# mother_card_rs_247pm.net
KiCad netlist of a schematic drawn in EAGLE
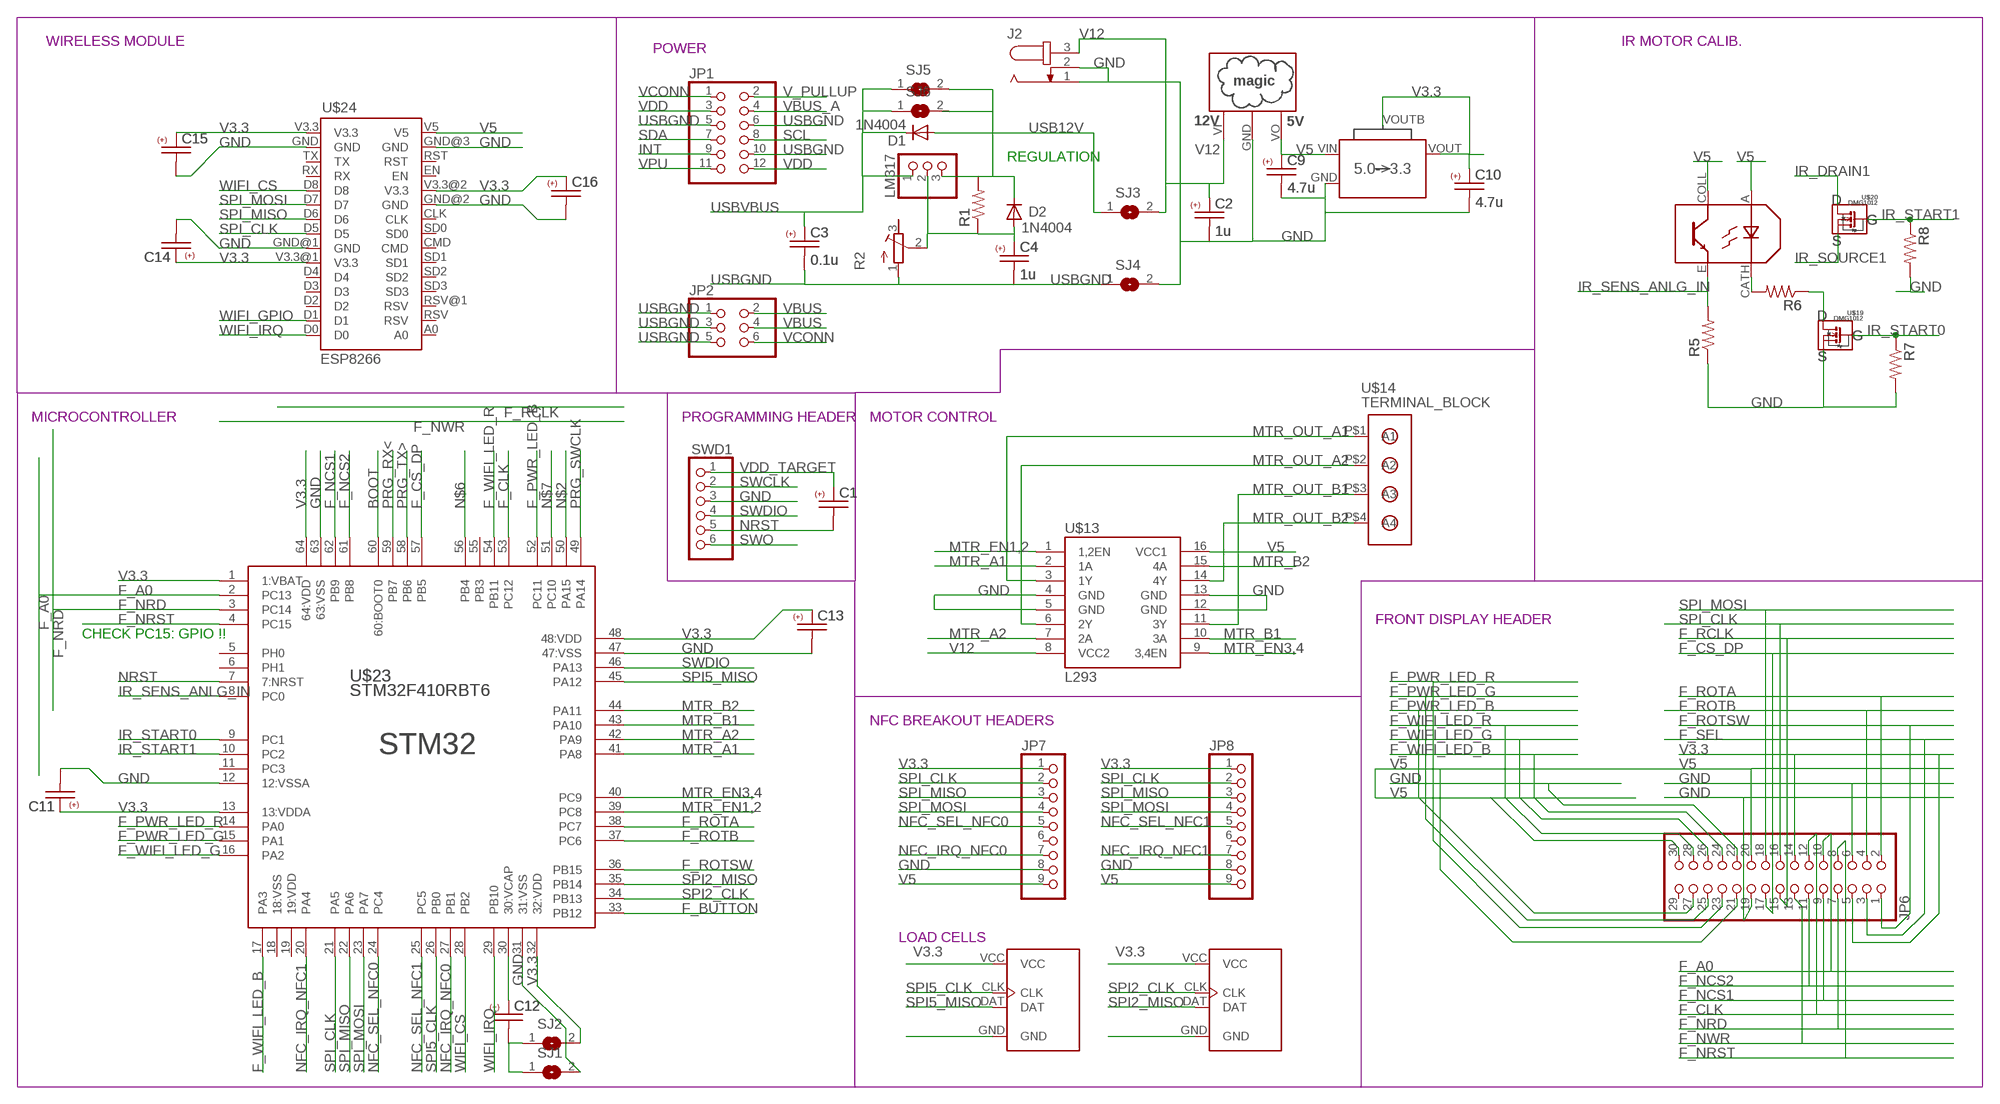
[diagram p0: schematic, sheet 1]

(export (version "E")
  (design (tool "Eeschema 10.0.6"))
  (components
    (comp (ref "C1")
      (value "C-USC0805")
      (footprint "eagle-import:C0805")
      (libsource (lib "eagle-import") (part "C-USC0805"))
    )
    (comp (ref "C2")
      (value "1u")
      (footprint "eagle-import:C0805")
      (libsource (lib "eagle-import") (part "C-USC0805"))
    )
    (comp (ref "C3")
      (value "0.1u")
      (footprint "eagle-import:C0805")
      (libsource (lib "eagle-import") (part "C-USC0805"))
    )
    (comp (ref "C4")
      (value "1u")
      (footprint "eagle-import:C0805")
      (libsource (lib "eagle-import") (part "C-USC0805"))
    )
    (comp (ref "C9")
      (value "4.7u")
      (footprint "eagle-import:C0805")
      (libsource (lib "eagle-import") (part "C-USC0805"))
    )
    (comp (ref "C10")
      (value "4.7u")
      (footprint "eagle-import:C0805")
      (libsource (lib "eagle-import") (part "C-USC0805"))
    )
    (comp (ref "C11")
      (value "C-USC0805")
      (footprint "eagle-import:C0805")
      (libsource (lib "eagle-import") (part "C-USC0805"))
    )
    (comp (ref "C12")
      (value "C-USC0805")
      (footprint "eagle-import:C0805")
      (libsource (lib "eagle-import") (part "C-USC0805"))
    )
    (comp (ref "C13")
      (value "C-USC0805")
      (footprint "eagle-import:C0805")
      (libsource (lib "eagle-import") (part "C-USC0805"))
    )
    (comp (ref "C14")
      (value "C-USC0805")
      (footprint "eagle-import:C0805")
      (libsource (lib "eagle-import") (part "C-USC0805"))
    )
    (comp (ref "C15")
      (value "C-USC0805")
      (footprint "eagle-import:C0805")
      (libsource (lib "eagle-import") (part "C-USC0805"))
    )
    (comp (ref "C16")
      (value "C-USC0805")
      (footprint "eagle-import:C0805")
      (libsource (lib "eagle-import") (part "C-USC0805"))
    )
    (comp (ref "D1")
      (value "1N4004")
      (footprint "eagle-import:DO41-10")
      (libsource (lib "eagle-import") (part "1N4004"))
    )
    (comp (ref "D2")
      (value "1N4004")
      (footprint "eagle-import:DO41-10")
      (libsource (lib "eagle-import") (part "1N4004"))
    )
    (comp (ref "J2")
      (value "JACK-PLUG0")
      (footprint "eagle-import:SPC4077")
      (libsource (lib "eagle-import") (part "JACK-PLUG0"))
    )
    (comp (ref "JP1")
      (value "PINHD-2X6")
      (footprint "eagle-import:2X06")
      (libsource (lib "eagle-import") (part "PINHD-2X6"))
    )
    (comp (ref "JP2")
      (value "PINHD-2X3")
      (footprint "eagle-import:2X03")
      (libsource (lib "eagle-import") (part "PINHD-2X3"))
    )
    (comp (ref "JP6")
      (value "PINHD-2X15/SOCK")
      (footprint "eagle-import:2X15_SOCK")
      (libsource (lib "eagle-import") (part "PINHD-2X15/SOCK"))
    )
    (comp (ref "JP7")
      (value "PINHD-1X9/90")
      (footprint "eagle-import:1X09_90")
      (libsource (lib "eagle-import") (part "PINHD-1X9/90"))
    )
    (comp (ref "JP8")
      (value "PINHD-1X9/90")
      (footprint "eagle-import:1X09_90")
      (libsource (lib "eagle-import") (part "PINHD-1X9/90"))
    )
    (comp (ref "LM317")
      (value "PINHD-1X3")
      (footprint "eagle-import:1X03")
      (libsource (lib "eagle-import") (part "PINHD-1X3"))
    )
    (comp (ref "R1")
      (value "R-US_R0805")
      (footprint "eagle-import:R0805")
      (libsource (lib "eagle-import") (part "R-US_R0805"))
    )
    (comp (ref "R2")
      (value "R-TRIMM64W")
      (footprint "eagle-import:RTRIM64W")
      (libsource (lib "eagle-import") (part "R-TRIMM64W"))
    )
    (comp (ref "R5")
      (value "R-US_R0805")
      (footprint "eagle-import:R0805")
      (libsource (lib "eagle-import") (part "R-US_R0805"))
    )
    (comp (ref "R6")
      (value "R-US_R0805")
      (footprint "eagle-import:R0805")
      (libsource (lib "eagle-import") (part "R-US_R0805"))
    )
    (comp (ref "R7")
      (value "R-US_R0805")
      (footprint "eagle-import:R0805")
      (libsource (lib "eagle-import") (part "R-US_R0805"))
    )
    (comp (ref "R8")
      (value "R-US_R0805")
      (footprint "eagle-import:R0805")
      (libsource (lib "eagle-import") (part "R-US_R0805"))
    )
    (comp (ref "SJ1") (value "SJ") (footprint "eagle-import:SJ") (libsource (lib "eagle-import") (part "SJ")))
    (comp (ref "SJ2") (value "SJ") (footprint "eagle-import:SJ") (libsource (lib "eagle-import") (part "SJ")))
    (comp (ref "SJ3") (value "SJ") (footprint "eagle-import:SJ") (libsource (lib "eagle-import") (part "SJ")))
    (comp (ref "SJ4") (value "SJ") (footprint "eagle-import:SJ") (libsource (lib "eagle-import") (part "SJ")))
    (comp (ref "SJ5") (value "SJ") (footprint "eagle-import:SJ") (libsource (lib "eagle-import") (part "SJ")))
    (comp (ref "SJ6") (value "SJ") (footprint "eagle-import:SJ") (libsource (lib "eagle-import") (part "SJ")))
    (comp (ref "SWD1")
      (value "PINHD-1X6")
      (footprint "eagle-import:1X06")
      (libsource (lib "eagle-import") (part "PINHD-1X6"))
    )
    (comp (ref "U$13")
      (value "L293")
      (footprint "eagle-import:DIL16")
      (libsource (lib "eagle-import") (part "L293"))
    )
    (comp (ref "U$14")
      (value "TERMINAL_BLOCK")
      (footprint "eagle-import:1X4_BLOCK")
      (libsource (lib "eagle-import") (part "TERMINAL_BLOCK"))
    )
    (comp (ref "U$15")
      (value "AP2114H")
      (footprint "eagle-import:AP2114H")
      (libsource (lib "eagle-import") (part "AP2114H"))
    )
    (comp (ref "U$16")
      (value "OKI-78SR-W36")
      (footprint "eagle-import:SIP3")
      (libsource (lib "eagle-import") (part "OKI-78SR-W36"))
    )
    (comp (ref "U$18")
      (value "TCRT5000")
      (footprint "eagle-import:TCRT5000")
      (libsource (lib "eagle-import") (part "TCRT5000"))
    )
    (comp (ref "U$19")
      (value "DMG1012")
      (footprint "eagle-import:SOT323")
      (libsource (lib "eagle-import") (part "DMG1012"))
    )
    (comp (ref "U$20")
      (value "DMG1012")
      (footprint "eagle-import:SOT323")
      (libsource (lib "eagle-import") (part "DMG1012"))
    )
    (comp (ref "U$21")
      (value "HX711")
      (footprint "eagle-import:HX711")
      (libsource (lib "eagle-import") (part "HX711"))
    )
    (comp (ref "U$22")
      (value "HX711")
      (footprint "eagle-import:HX711")
      (libsource (lib "eagle-import") (part "HX711"))
    )
    (comp (ref "U$23")
      (value "STM32F410RBT6")
      (footprint "eagle-import:QFP50P1200X1200X160-64N")
      (libsource (lib "eagle-import") (part "STM32F410RBT6"))
    )
    (comp (ref "U$24")
      (value "ESP8266")
      (footprint "eagle-import:ESP8266")
      (libsource (lib "eagle-import") (part "ESP8266"))
    )
  )
  (nets
    (net (code "1") (name "/BOOT") (class "Default")
      (node (ref "U$23") (pin "60") (pinfunction "60:BOOT0_60") (pintype "bidirectional"))
    )
    (net (code "2") (name "/F_A0") (class "Default")
      (node (ref "JP6") (pin "10") (pinfunction "10_10") (pintype "passive"))
      (node (ref "U$23") (pin "2") (pinfunction "PC13_2") (pintype "bidirectional"))
    )
    (net (code "3") (name "/F_BUTTON") (class "Default")
      (node (ref "U$23") (pin "33") (pinfunction "PB12_33") (pintype "bidirectional"))
    )
    (net (code "4") (name "/F_CLK") (class "Default")
      (node (ref "JP6") (pin "12") (pinfunction "12_12") (pintype "passive"))
      (node (ref "U$23") (pin "53") (pinfunction "PC12_53") (pintype "bidirectional"))
    )
    (net (code "5") (name "/F_CS_DP") (class "Default")
      (node (ref "JP6") (pin "17") (pinfunction "17_17") (pintype "passive"))
      (node (ref "U$23") (pin "57") (pinfunction "PB5_57") (pintype "bidirectional"))
    )
    (net (code "6") (name "/F_NCS1") (class "Default")
      (node (ref "JP6") (pin "9") (pinfunction "9_9") (pintype "passive"))
      (node (ref "U$23") (pin "62") (pinfunction "PB9_62") (pintype "bidirectional"))
    )
    (net (code "7") (name "/F_NCS2") (class "Default")
      (node (ref "JP6") (pin "11") (pinfunction "11_11") (pintype "passive"))
      (node (ref "U$23") (pin "61") (pinfunction "PB8_61") (pintype "bidirectional"))
    )
    (net (code "8") (name "/F_NRD") (class "Default")
      (node (ref "JP6") (pin "7") (pinfunction "7_7") (pintype "passive"))
      (node (ref "U$23") (pin "3") (pinfunction "PC14_3") (pintype "bidirectional"))
    )
    (net (code "9") (name "/F_NRST") (class "Default")
      (node (ref "JP6") (pin "8") (pinfunction "8_8") (pintype "passive"))
      (node (ref "U$23") (pin "4") (pinfunction "PC15_4") (pintype "bidirectional"))
    )
    (net (code "10") (name "/F_NWR") (class "Default")
      (node (ref "JP6") (pin "13") (pinfunction "13_13") (pintype "passive"))
    )
    (net (code "11") (name "/F_PWR_LED_B") (class "Default")
      (node (ref "JP6") (pin "27") (pinfunction "27_27") (pintype "passive"))
      (node (ref "U$23") (pin "52") (pinfunction "PC11_52") (pintype "bidirectional"))
    )
    (net (code "12") (name "/F_PWR_LED_G") (class "Default")
      (node (ref "JP6") (pin "25") (pinfunction "25_25") (pintype "passive"))
      (node (ref "U$23") (pin "15") (pinfunction "PA1_15") (pintype "bidirectional"))
    )
    (net (code "13") (name "/F_PWR_LED_R") (class "Default")
      (node (ref "JP6") (pin "23") (pinfunction "23_23") (pintype "passive"))
      (node (ref "U$23") (pin "14") (pinfunction "PA0_14") (pintype "bidirectional"))
    )
    (net (code "14") (name "/F_RCLK") (class "Default")
      (node (ref "JP6") (pin "15") (pinfunction "15_15") (pintype "passive"))
    )
    (net (code "15") (name "/F_ROTA") (class "Default")
      (node (ref "JP6") (pin "2") (pinfunction "2_2") (pintype "passive"))
      (node (ref "U$23") (pin "38") (pinfunction "PC7_38") (pintype "bidirectional"))
    )
    (net (code "16") (name "/F_ROTB") (class "Default")
      (node (ref "JP6") (pin "4") (pinfunction "4_4") (pintype "passive"))
      (node (ref "U$23") (pin "37") (pinfunction "PC6_37") (pintype "bidirectional"))
    )
    (net (code "17") (name "/F_ROTSW") (class "Default")
      (node (ref "JP6") (pin "1") (pinfunction "1_1") (pintype "passive"))
      (node (ref "U$23") (pin "36") (pinfunction "PB15_36") (pintype "bidirectional"))
    )
    (net (code "18") (name "/F_SEL") (class "Default")
      (node (ref "JP6") (pin "3") (pinfunction "3_3") (pintype "passive"))
    )
    (net (code "19") (name "/F_WIFI_LED_B") (class "Default")
      (node (ref "JP6") (pin "24") (pinfunction "24_24") (pintype "passive"))
      (node (ref "U$23") (pin "17") (pinfunction "PA3_17") (pintype "bidirectional"))
    )
    (net (code "20") (name "/F_WIFI_LED_G") (class "Default")
      (node (ref "JP6") (pin "26") (pinfunction "26_26") (pintype "passive"))
      (node (ref "U$23") (pin "16") (pinfunction "PA2_16") (pintype "bidirectional"))
    )
    (net (code "21") (name "/F_WIFI_LED_R") (class "Default")
      (node (ref "JP6") (pin "28") (pinfunction "28_28") (pintype "passive"))
      (node (ref "U$23") (pin "54") (pinfunction "PB11_54") (pintype "bidirectional"))
    )
    (net (code "22") (name "/GND") (class "Default")
      (node (ref "C10") (pin "2") (pinfunction "2_2") (pintype "passive"))
      (node (ref "C11") (pin "2") (pinfunction "2_2") (pintype "passive"))
      (node (ref "C13") (pin "2") (pinfunction "2_2") (pintype "passive"))
      (node (ref "C14") (pin "2") (pinfunction "2_2") (pintype "passive"))
      (node (ref "C15") (pin "2") (pinfunction "2_2") (pintype "passive"))
      (node (ref "C16") (pin "2") (pinfunction "2_2") (pintype "passive"))
      (node (ref "C2") (pin "2") (pinfunction "2_2") (pintype "passive"))
      (node (ref "C9") (pin "2") (pinfunction "2_2") (pintype "passive"))
      (node (ref "J2") (pin "1") (pinfunction "1_1") (pintype "passive"))
      (node (ref "J2") (pin "2") (pinfunction "2_2") (pintype "passive"))
      (node (ref "JP6") (pin "19") (pinfunction "19_19") (pintype "passive"))
      (node (ref "JP6") (pin "22") (pinfunction "22_22") (pintype "passive"))
      (node (ref "JP6") (pin "6") (pinfunction "6_6") (pintype "passive"))
      (node (ref "JP7") (pin "8") (pinfunction "8_8") (pintype "passive"))
      (node (ref "JP8") (pin "8") (pinfunction "8_8") (pintype "passive"))
      (node (ref "R5") (pin "1") (pinfunction "1_1") (pintype "passive"))
      (node (ref "R7") (pin "2") (pinfunction "2_2") (pintype "passive"))
      (node (ref "R8") (pin "2") (pinfunction "2_2") (pintype "passive"))
      (node (ref "SJ1") (pin "2") (pinfunction "2_2") (pintype "passive"))
      (node (ref "SJ4") (pin "2") (pinfunction "2_2") (pintype "passive"))
      (node (ref "SWD1") (pin "3") (pinfunction "3_3") (pintype "passive"))
      (node (ref "U$13") (pin "12") (pinfunction "GND_12") (pintype "bidirectional"))
      (node (ref "U$13") (pin "13") (pinfunction "GND_13") (pintype "bidirectional"))
      (node (ref "U$13") (pin "4") (pinfunction "GND_4") (pintype "bidirectional"))
      (node (ref "U$13") (pin "5") (pinfunction "GND_5") (pintype "bidirectional"))
      (node (ref "U$15") (pin "GND") (pinfunction "GND_GND") (pintype "power_in"))
      (node (ref "U$16") (pin "GND") (pinfunction "P$2_GND") (pintype "power_in"))
      (node (ref "U$19") (pin "S") (pinfunction "S_S") (pintype "bidirectional"))
      (node (ref "U$21") (pin "GND") (pinfunction "GND_GND") (pintype "power_in"))
      (node (ref "U$22") (pin "GND") (pinfunction "GND_GND") (pintype "power_in"))
      (node (ref "U$23") (pin "12") (pinfunction "12:VSSA_12") (pintype "bidirectional"))
      (node (ref "U$23") (pin "31") (pinfunction "31:VSS_31") (pintype "bidirectional"))
      (node (ref "U$23") (pin "47") (pinfunction "47:VSS_47") (pintype "bidirectional"))
      (node (ref "U$23") (pin "63") (pinfunction "63:VSS_63") (pintype "bidirectional"))
      (node (ref "U$24") (pin "GND") (pinfunction "GND_GND") (pintype "bidirectional"))
      (node (ref "U$24") (pin "GND@1") (pinfunction "GND_GND@1") (pintype "bidirectional"))
      (node (ref "U$24") (pin "GND@2") (pinfunction "GND_GND@2") (pintype "bidirectional"))
      (node (ref "U$24") (pin "GND@3") (pinfunction "GND_GND@3") (pintype "bidirectional"))
    )
    (net (code "23") (name "/INT") (class "Default")
      (node (ref "JP1") (pin "9") (pinfunction "9_9") (pintype "passive"))
    )
    (net (code "24") (name "/IR_DRAIN1") (class "Default")
      (node (ref "U$20") (pin "D") (pinfunction "D_D") (pintype "bidirectional"))
    )
    (net (code "25") (name "/IR_SENS_ANLG_IN") (class "Default")
      (node (ref "R5") (pin "2") (pinfunction "2_2") (pintype "passive"))
      (node (ref "U$18") (pin "E") (pinfunction "E_E") (pintype "bidirectional"))
      (node (ref "U$23") (pin "8") (pinfunction "PC0_8") (pintype "bidirectional"))
    )
    (net (code "26") (name "/IR_SOURCE1") (class "Default")
      (node (ref "U$20") (pin "S") (pinfunction "S_S") (pintype "bidirectional"))
    )
    (net (code "27") (name "/IR_START0") (class "Default")
      (node (ref "R7") (pin "1") (pinfunction "1_1") (pintype "passive"))
      (node (ref "U$19") (pin "G") (pinfunction "G_G") (pintype "bidirectional"))
      (node (ref "U$23") (pin "9") (pinfunction "PC1_9") (pintype "bidirectional"))
    )
    (net (code "28") (name "/IR_START1") (class "Default")
      (node (ref "R8") (pin "1") (pinfunction "1_1") (pintype "passive"))
      (node (ref "U$20") (pin "G") (pinfunction "G_G") (pintype "bidirectional"))
      (node (ref "U$23") (pin "10") (pinfunction "PC2_10") (pintype "bidirectional"))
    )
    (net (code "29") (name "/MTR_A1") (class "Default")
      (node (ref "U$13") (pin "2") (pinfunction "1A_2") (pintype "bidirectional"))
      (node (ref "U$23") (pin "41") (pinfunction "PA8_41") (pintype "bidirectional"))
    )
    (net (code "30") (name "/MTR_A2") (class "Default")
      (node (ref "U$13") (pin "7") (pinfunction "2A_7") (pintype "bidirectional"))
      (node (ref "U$23") (pin "42") (pinfunction "PA9_42") (pintype "bidirectional"))
    )
    (net (code "31") (name "/MTR_B1") (class "Default")
      (node (ref "U$13") (pin "10") (pinfunction "3A_10") (pintype "bidirectional"))
      (node (ref "U$23") (pin "43") (pinfunction "PA10_43") (pintype "bidirectional"))
    )
    (net (code "32") (name "/MTR_B2") (class "Default")
      (node (ref "U$13") (pin "15") (pinfunction "4A_15") (pintype "bidirectional"))
      (node (ref "U$23") (pin "44") (pinfunction "PA11_44") (pintype "bidirectional"))
    )
    (net (code "33") (name "/MTR_EN1,2") (class "Default")
      (node (ref "U$13") (pin "1") (pinfunction "1,2EN_1") (pintype "bidirectional"))
      (node (ref "U$23") (pin "39") (pinfunction "PC8_39") (pintype "bidirectional"))
    )
    (net (code "34") (name "/MTR_EN3,4") (class "Default")
      (node (ref "U$13") (pin "9") (pinfunction "3,4EN_9") (pintype "bidirectional"))
      (node (ref "U$23") (pin "40") (pinfunction "PC9_40") (pintype "bidirectional"))
    )
    (net (code "35") (name "/MTR_OUT_A1") (class "Default")
      (node (ref "U$13") (pin "3") (pinfunction "1Y_3") (pintype "bidirectional"))
      (node (ref "U$14") (pin "P$1") (pinfunction "A1_P$1") (pintype "bidirectional"))
    )
    (net (code "36") (name "/MTR_OUT_A2") (class "Default")
      (node (ref "U$13") (pin "6") (pinfunction "2Y_6") (pintype "bidirectional"))
      (node (ref "U$14") (pin "P$2") (pinfunction "A2_P$2") (pintype "bidirectional"))
    )
    (net (code "37") (name "/MTR_OUT_B1") (class "Default")
      (node (ref "U$13") (pin "11") (pinfunction "3Y_11") (pintype "bidirectional"))
      (node (ref "U$14") (pin "P$3") (pinfunction "A3_P$3") (pintype "bidirectional"))
    )
    (net (code "38") (name "/MTR_OUT_B2") (class "Default")
      (node (ref "U$13") (pin "14") (pinfunction "4Y_14") (pintype "bidirectional"))
      (node (ref "U$14") (pin "P$4") (pinfunction "A4_P$4") (pintype "bidirectional"))
    )
    (net (code "39") (name "/N$2") (class "Default")
      (node (ref "U$23") (pin "50") (pinfunction "PA15_50") (pintype "bidirectional"))
    )
    (net (code "40") (name "/N$6") (class "Default")
      (node (ref "U$23") (pin "56") (pinfunction "PB4_56") (pintype "bidirectional"))
    )
    (net (code "41") (name "/N$7") (class "Default")
      (node (ref "U$23") (pin "51") (pinfunction "PC10_51") (pintype "bidirectional"))
    )
    (net (code "42") (name "/NFC_IRQ_NFC0") (class "Default")
      (node (ref "JP7") (pin "7") (pinfunction "7_7") (pintype "passive"))
      (node (ref "U$23") (pin "27") (pinfunction "PB1_27") (pintype "bidirectional"))
    )
    (net (code "43") (name "/NFC_IRQ_NFC1") (class "Default")
      (node (ref "JP8") (pin "7") (pinfunction "7_7") (pintype "passive"))
      (node (ref "U$23") (pin "20") (pinfunction "PA4_20") (pintype "bidirectional"))
    )
    (net (code "44") (name "/NFC_SEL_NFC0") (class "Default")
      (node (ref "JP7") (pin "5") (pinfunction "5_5") (pintype "passive"))
      (node (ref "U$23") (pin "24") (pinfunction "PC4_24") (pintype "bidirectional"))
    )
    (net (code "45") (name "/NFC_SEL_NFC1") (class "Default")
      (node (ref "JP8") (pin "5") (pinfunction "5_5") (pintype "passive"))
      (node (ref "U$23") (pin "25") (pinfunction "PC5_25") (pintype "bidirectional"))
    )
    (net (code "46") (name "/NRST") (class "Default")
      (node (ref "C1") (pin "2") (pinfunction "2_2") (pintype "passive"))
      (node (ref "SWD1") (pin "5") (pinfunction "5_5") (pintype "passive"))
      (node (ref "U$23") (pin "7") (pinfunction "7:NRST_7") (pintype "bidirectional"))
    )
    (net (code "47") (name "/PRG_RX<") (class "Default")
      (node (ref "U$23") (pin "59") (pinfunction "PB7_59") (pintype "bidirectional"))
    )
    (net (code "48") (name "/PRG_SWCLK") (class "Default")
      (node (ref "U$23") (pin "49") (pinfunction "PA14_49") (pintype "bidirectional"))
    )
    (net (code "49") (name "/PRG_TX>") (class "Default")
      (node (ref "U$23") (pin "58") (pinfunction "PB6_58") (pintype "bidirectional"))
    )
    (net (code "50") (name "/SCL") (class "Default")
      (node (ref "JP1") (pin "8") (pinfunction "8_8") (pintype "passive"))
    )
    (net (code "51") (name "/SDA") (class "Default")
      (node (ref "JP1") (pin "7") (pinfunction "7_7") (pintype "passive"))
    )
    (net (code "52") (name "/SPI2_CLK") (class "Default")
      (node (ref "U$22") (pin "CLK") (pinfunction "CLK_CLK") (pintype "bidirectional"))
      (node (ref "U$23") (pin "34") (pinfunction "PB13_34") (pintype "bidirectional"))
    )
    (net (code "53") (name "/SPI2_MISO") (class "Default")
      (node (ref "U$22") (pin "DAT") (pinfunction "DAT_DAT") (pintype "bidirectional"))
      (node (ref "U$23") (pin "35") (pinfunction "PB14_35") (pintype "bidirectional"))
    )
    (net (code "54") (name "/SPI5_CLK") (class "Default")
      (node (ref "U$21") (pin "CLK") (pinfunction "CLK_CLK") (pintype "bidirectional"))
      (node (ref "U$23") (pin "26") (pinfunction "PB0_26") (pintype "bidirectional"))
    )
    (net (code "55") (name "/SPI5_MISO") (class "Default")
      (node (ref "U$21") (pin "DAT") (pinfunction "DAT_DAT") (pintype "bidirectional"))
      (node (ref "U$23") (pin "45") (pinfunction "PA12_45") (pintype "bidirectional"))
    )
    (net (code "56") (name "/SPI_CLK") (class "Default")
      (node (ref "JP6") (pin "16") (pinfunction "16_16") (pintype "passive"))
      (node (ref "JP7") (pin "2") (pinfunction "2_2") (pintype "passive"))
      (node (ref "JP8") (pin "2") (pinfunction "2_2") (pintype "passive"))
      (node (ref "U$23") (pin "21") (pinfunction "PA5_21") (pintype "bidirectional"))
      (node (ref "U$24") (pin "D5") (pinfunction "D5_D5") (pintype "bidirectional"))
    )
    (net (code "57") (name "/SPI_MISO") (class "Default")
      (node (ref "JP7") (pin "3") (pinfunction "3_3") (pintype "passive"))
      (node (ref "JP8") (pin "3") (pinfunction "3_3") (pintype "passive"))
      (node (ref "U$23") (pin "22") (pinfunction "PA6_22") (pintype "bidirectional"))
      (node (ref "U$24") (pin "D6") (pinfunction "D6_D6") (pintype "bidirectional"))
    )
    (net (code "58") (name "/SPI_MOSI") (class "Default")
      (node (ref "JP6") (pin "18") (pinfunction "18_18") (pintype "passive"))
      (node (ref "JP7") (pin "4") (pinfunction "4_4") (pintype "passive"))
      (node (ref "JP8") (pin "4") (pinfunction "4_4") (pintype "passive"))
      (node (ref "U$23") (pin "23") (pinfunction "PA7_23") (pintype "bidirectional"))
      (node (ref "U$24") (pin "D7") (pinfunction "D7_D7") (pintype "bidirectional"))
    )
    (net (code "59") (name "/SWCLK") (class "Default")
      (node (ref "SWD1") (pin "2") (pinfunction "2_2") (pintype "passive"))
    )
    (net (code "60") (name "/SWDIO") (class "Default")
      (node (ref "SWD1") (pin "4") (pinfunction "4_4") (pintype "passive"))
      (node (ref "U$23") (pin "46") (pinfunction "PA13_46") (pintype "bidirectional"))
    )
    (net (code "61") (name "/SWO") (class "Default")
      (node (ref "SWD1") (pin "6") (pinfunction "6_6") (pintype "passive"))
    )
    (net (code "62") (name "/USB12V") (class "Default")
      (node (ref "D1") (pin "A") (pinfunction "A_A") (pintype "passive"))
      (node (ref "D2") (pin "C") (pinfunction "C_C") (pintype "passive"))
      (node (ref "LM317") (pin "3") (pinfunction "3_3") (pintype "passive"))
      (node (ref "R1") (pin "2") (pinfunction "2_2") (pintype "passive"))
      (node (ref "SJ3") (pin "1") (pinfunction "1_1") (pintype "passive"))
      (node (ref "SJ5") (pin "2") (pinfunction "2_2") (pintype "passive"))
    )
    (net (code "63") (name "/USBGND") (class "Default")
      (node (ref "C3") (pin "2") (pinfunction "2_2") (pintype "passive"))
      (node (ref "C4") (pin "2") (pinfunction "2_2") (pintype "passive"))
      (node (ref "JP1") (pin "10") (pinfunction "10_10") (pintype "passive"))
      (node (ref "JP1") (pin "5") (pinfunction "5_5") (pintype "passive"))
      (node (ref "JP1") (pin "6") (pinfunction "6_6") (pintype "passive"))
      (node (ref "JP2") (pin "1") (pinfunction "1_1") (pintype "passive"))
      (node (ref "JP2") (pin "3") (pinfunction "3_3") (pintype "passive"))
      (node (ref "JP2") (pin "5") (pinfunction "5_5") (pintype "passive"))
      (node (ref "R2") (pin "1") (pinfunction "A_1") (pintype "passive"))
      (node (ref "SJ4") (pin "1") (pinfunction "1_1") (pintype "passive"))
    )
    (net (code "64") (name "/USBVBUS") (class "Default")
      (node (ref "C3") (pin "1") (pinfunction "1_1") (pintype "passive"))
      (node (ref "D1") (pin "C") (pinfunction "C_C") (pintype "passive"))
      (node (ref "LM317") (pin "1") (pinfunction "1_1") (pintype "passive"))
      (node (ref "SJ5") (pin "1") (pinfunction "1_1") (pintype "passive"))
      (node (ref "SJ6") (pin "1") (pinfunction "1_1") (pintype "passive"))
    )
    (net (code "65") (name "/V3.3") (class "Default")
      (node (ref "C10") (pin "1") (pinfunction "1_1") (pintype "passive"))
      (node (ref "C11") (pin "1") (pinfunction "1_1") (pintype "passive"))
      (node (ref "C13") (pin "1") (pinfunction "1_1") (pintype "passive"))
      (node (ref "C14") (pin "1") (pinfunction "1_1") (pintype "passive"))
      (node (ref "C15") (pin "1") (pinfunction "1_1") (pintype "passive"))
      (node (ref "C16") (pin "1") (pinfunction "1_1") (pintype "passive"))
      (node (ref "JP6") (pin "14") (pinfunction "14_14") (pintype "passive"))
      (node (ref "JP6") (pin "5") (pinfunction "5_5") (pintype "passive"))
      (node (ref "JP7") (pin "1") (pinfunction "1_1") (pintype "passive"))
      (node (ref "JP8") (pin "1") (pinfunction "1_1") (pintype "passive"))
      (node (ref "SJ2") (pin "2") (pinfunction "2_2") (pintype "passive"))
      (node (ref "U$15") (pin "VOUT") (pinfunction "VO_VOUT") (pintype "output"))
      (node (ref "U$15") (pin "VOUTB") (pinfunction "BODY_VOUTB") (pintype "open_collector"))
      (node (ref "U$21") (pin "VCC") (pinfunction "VCC_VCC") (pintype "power_in"))
      (node (ref "U$22") (pin "VCC") (pinfunction "VCC_VCC") (pintype "power_in"))
      (node (ref "U$23") (pin "1") (pinfunction "1:VBAT_1") (pintype "bidirectional"))
      (node (ref "U$23") (pin "13") (pinfunction "13:VDDA_13") (pintype "bidirectional"))
      (node (ref "U$23") (pin "32") (pinfunction "32:VDD_32") (pintype "bidirectional"))
      (node (ref "U$23") (pin "48") (pinfunction "48:VDD_48") (pintype "bidirectional"))
      (node (ref "U$23") (pin "64") (pinfunction "64:VDD_64") (pintype "bidirectional"))
      (node (ref "U$24") (pin "V3.3") (pinfunction "V3.3_V3.3") (pintype "bidirectional"))
      (node (ref "U$24") (pin "V3.3@1") (pinfunction "V3.3_V3.3@1") (pintype "bidirectional"))
      (node (ref "U$24") (pin "V3.3@2") (pinfunction "V3.3_V3.3@2") (pintype "bidirectional"))
    )
    (net (code "66") (name "/V5") (class "Default")
      (node (ref "C9") (pin "1") (pinfunction "1_1") (pintype "passive"))
      (node (ref "JP6") (pin "20") (pinfunction "20_20") (pintype "passive"))
      (node (ref "JP6") (pin "21") (pinfunction "21_21") (pintype "passive"))
      (node (ref "JP6") (pin "30") (pinfunction "30_30") (pintype "passive"))
      (node (ref "JP7") (pin "9") (pinfunction "9_9") (pintype "passive"))
      (node (ref "JP8") (pin "9") (pinfunction "9_9") (pintype "passive"))
      (node (ref "U$13") (pin "16") (pinfunction "VCC1_16") (pintype "bidirectional"))
      (node (ref "U$15") (pin "VIN") (pinfunction "VI_VIN") (pintype "input"))
      (node (ref "U$16") (pin "VO") (pinfunction "P$3_VO") (pintype "output"))
      (node (ref "U$18") (pin "A") (pinfunction "A_A") (pintype "bidirectional"))
      (node (ref "U$18") (pin "COLL") (pinfunction "COLL_COLL") (pintype "bidirectional"))
      (node (ref "U$24") (pin "V5") (pinfunction "V5_V5") (pintype "bidirectional"))
    )
    (net (code "67") (name "/V12") (class "Default")
      (node (ref "C2") (pin "1") (pinfunction "1_1") (pintype "passive"))
      (node (ref "J2") (pin "3") (pinfunction "3_3") (pintype "passive"))
      (node (ref "SJ3") (pin "2") (pinfunction "2_2") (pintype "passive"))
      (node (ref "U$13") (pin "8") (pinfunction "VCC2_8") (pintype "bidirectional"))
      (node (ref "U$16") (pin "VI") (pinfunction "P$1_VI") (pintype "input"))
    )
    (net (code "68") (name "/VBUS") (class "Default")
      (node (ref "JP2") (pin "2") (pinfunction "2_2") (pintype "passive"))
      (node (ref "JP2") (pin "4") (pinfunction "4_4") (pintype "passive"))
    )
    (net (code "69") (name "/VBUS_A") (class "Default")
      (node (ref "JP1") (pin "4") (pinfunction "4_4") (pintype "passive"))
    )
    (net (code "70") (name "/VCONN") (class "Default")
      (node (ref "JP1") (pin "1") (pinfunction "1_1") (pintype "passive"))
      (node (ref "JP2") (pin "6") (pinfunction "6_6") (pintype "passive"))
    )
    (net (code "71") (name "/VDD") (class "Default")
      (node (ref "JP1") (pin "12") (pinfunction "12_12") (pintype "passive"))
      (node (ref "JP1") (pin "3") (pinfunction "3_3") (pintype "passive"))
    )
    (net (code "72") (name "/VDD_TARGET") (class "Default")
      (node (ref "C1") (pin "1") (pinfunction "1_1") (pintype "passive"))
      (node (ref "SWD1") (pin "1") (pinfunction "1_1") (pintype "passive"))
    )
    (net (code "73") (name "/VPU") (class "Default")
      (node (ref "JP1") (pin "11") (pinfunction "11_11") (pintype "passive"))
    )
    (net (code "74") (name "/V_PULLUP") (class "Default")
      (node (ref "JP1") (pin "2") (pinfunction "2_2") (pintype "passive"))
    )
    (net (code "75") (name "/WIFI_CS") (class "Default")
      (node (ref "U$23") (pin "28") (pinfunction "PB2_28") (pintype "bidirectional"))
      (node (ref "U$24") (pin "D8") (pinfunction "D8_D8") (pintype "bidirectional"))
    )
    (net (code "76") (name "/WIFI_GPIO") (class "Default")
      (node (ref "U$24") (pin "D1") (pinfunction "D1_D1") (pintype "bidirectional"))
    )
    (net (code "77") (name "/WIFI_IRQ") (class "Default")
      (node (ref "U$23") (pin "29") (pinfunction "PB10_29") (pintype "bidirectional"))
      (node (ref "U$24") (pin "D0") (pinfunction "D0_D0") (pintype "bidirectional"))
    )
    (net (code "78") (name "Net-(C12-Pad2)") (class "Default")
      (node (ref "C12") (pin "2") (pinfunction "2_2") (pintype "passive"))
      (node (ref "SJ1") (pin "1") (pinfunction "1_1") (pintype "passive"))
      (node (ref "SJ2") (pin "1") (pinfunction "1_1") (pintype "passive"))
    )
    (net (code "79") (name "Net-(R2-S)") (class "Default")
      (node (ref "C4") (pin "1") (pinfunction "1_1") (pintype "passive"))
      (node (ref "D2") (pin "A") (pinfunction "A_A") (pintype "passive"))
      (node (ref "LM317") (pin "2") (pinfunction "2_2") (pintype "passive"))
      (node (ref "R1") (pin "1") (pinfunction "1_1") (pintype "passive"))
      (node (ref "R2") (pin "2") (pinfunction "S_2") (pintype "passive"))
    )
    (net (code "80") (name "Net-(R6-Pad1)") (class "Default")
      (node (ref "R6") (pin "1") (pinfunction "1_1") (pintype "passive"))
      (node (ref "U$19") (pin "D") (pinfunction "D_D") (pintype "bidirectional"))
    )
    (net (code "81") (name "Net-(R6-Pad2)") (class "Default")
      (node (ref "R6") (pin "2") (pinfunction "2_2") (pintype "passive"))
      (node (ref "U$18") (pin "CATH") (pinfunction "CATH_CATH") (pintype "bidirectional"))
    )
    (net (code "82") (name "Net-(U$23-30:VCAP)") (class "Default")
      (node (ref "C12") (pin "1") (pinfunction "1_1") (pintype "passive"))
      (node (ref "U$23") (pin "30") (pinfunction "30:VCAP_30") (pintype "bidirectional"))
    )
    (net (code "83") (name "unconnected-(JP6-Pad29)") (class "Default")
      (node (ref "JP6") (pin "29") (pinfunction "29_29") (pintype "passive"))
    )
    (net (code "84") (name "unconnected-(JP7-Pad6)") (class "Default")
      (node (ref "JP7") (pin "6") (pinfunction "6_6") (pintype "passive"))
    )
    (net (code "85") (name "unconnected-(JP8-Pad6)") (class "Default")
      (node (ref "JP8") (pin "6") (pinfunction "6_6") (pintype "passive"))
    )
    (net (code "86") (name "unconnected-(R2-E-Pad3)") (class "Default")
      (node (ref "R2") (pin "3") (pinfunction "E_3") (pintype "passive"))
    )
    (net (code "87") (name "unconnected-(SJ6-Pad2)") (class "Default")
      (node (ref "SJ6") (pin "2") (pinfunction "2_2") (pintype "passive"))
    )
    (net (code "88") (name "unconnected-(U$23-18:VSS-Pad18)") (class "Default")
      (node (ref "U$23") (pin "18") (pinfunction "18:VSS_18") (pintype "bidirectional"))
    )
    (net (code "89") (name "unconnected-(U$23-19:VDD-Pad19)") (class "Default")
      (node (ref "U$23") (pin "19") (pinfunction "19:VDD_19") (pintype "bidirectional"))
    )
    (net (code "90") (name "unconnected-(U$23-PB3-Pad55)") (class "Default")
      (node (ref "U$23") (pin "55") (pinfunction "PB3_55") (pintype "bidirectional"))
    )
    (net (code "91") (name "unconnected-(U$23-PC3-Pad11)") (class "Default")
      (node (ref "U$23") (pin "11") (pinfunction "PC3_11") (pintype "bidirectional"))
    )
    (net (code "92") (name "unconnected-(U$23-PH0-Pad5)") (class "Default")
      (node (ref "U$23") (pin "5") (pinfunction "PH0_5") (pintype "bidirectional"))
    )
    (net (code "93") (name "unconnected-(U$23-PH1-Pad6)") (class "Default")
      (node (ref "U$23") (pin "6") (pinfunction "PH1_6") (pintype "bidirectional"))
    )
    (net (code "94") (name "unconnected-(U$24-PadA0)") (class "Default")
      (node (ref "U$24") (pin "A0") (pinfunction "A0_A0") (pintype "bidirectional"))
    )
    (net (code "95") (name "unconnected-(U$24-PadCLK)") (class "Default")
      (node (ref "U$24") (pin "CLK") (pinfunction "CLK_CLK") (pintype "bidirectional"))
    )
    (net (code "96") (name "unconnected-(U$24-PadCMD)") (class "Default")
      (node (ref "U$24") (pin "CMD") (pinfunction "CMD_CMD") (pintype "bidirectional"))
    )
    (net (code "97") (name "unconnected-(U$24-PadD2)") (class "Default")
      (node (ref "U$24") (pin "D2") (pinfunction "D2_D2") (pintype "bidirectional"))
    )
    (net (code "98") (name "unconnected-(U$24-PadD3)") (class "Default")
      (node (ref "U$24") (pin "D3") (pinfunction "D3_D3") (pintype "bidirectional"))
    )
    (net (code "99") (name "unconnected-(U$24-PadD4)") (class "Default")
      (node (ref "U$24") (pin "D4") (pinfunction "D4_D4") (pintype "bidirectional"))
    )
    (net (code "100") (name "unconnected-(U$24-PadEN)") (class "Default")
      (node (ref "U$24") (pin "EN") (pinfunction "EN_EN") (pintype "bidirectional"))
    )
    (net (code "101") (name "unconnected-(U$24-PadRST)") (class "Default")
      (node (ref "U$24") (pin "RST") (pinfunction "RST_RST") (pintype "bidirectional"))
    )
    (net (code "102") (name "unconnected-(U$24-PadRSV)") (class "Default")
      (node (ref "U$24") (pin "RSV") (pinfunction "RSV_RSV") (pintype "bidirectional"))
    )
    (net (code "103") (name "unconnected-(U$24-PadRX)") (class "Default")
      (node (ref "U$24") (pin "RX") (pinfunction "RX_RX") (pintype "bidirectional"))
    )
    (net (code "104") (name "unconnected-(U$24-PadSD0)") (class "Default")
      (node (ref "U$24") (pin "SD0") (pinfunction "SD0_SD0") (pintype "bidirectional"))
    )
    (net (code "105") (name "unconnected-(U$24-PadSD1)") (class "Default")
      (node (ref "U$24") (pin "SD1") (pinfunction "SD1_SD1") (pintype "bidirectional"))
    )
    (net (code "106") (name "unconnected-(U$24-PadSD2)") (class "Default")
      (node (ref "U$24") (pin "SD2") (pinfunction "SD2_SD2") (pintype "bidirectional"))
    )
    (net (code "107") (name "unconnected-(U$24-PadSD3)") (class "Default")
      (node (ref "U$24") (pin "SD3") (pinfunction "SD3_SD3") (pintype "bidirectional"))
    )
    (net (code "108") (name "unconnected-(U$24-PadTX)") (class "Default")
      (node (ref "U$24") (pin "TX") (pinfunction "TX_TX") (pintype "bidirectional"))
    )
    (net (code "109") (name "unconnected-(U$24-RSV-PadRSV@1)") (class "Default")
      (node (ref "U$24") (pin "RSV@1") (pinfunction "RSV_RSV@1") (pintype "bidirectional"))
    )
  )
)
